# AVR16_BlueBoard.net
KiCad netlist of a schematic drawn in Altium Designer
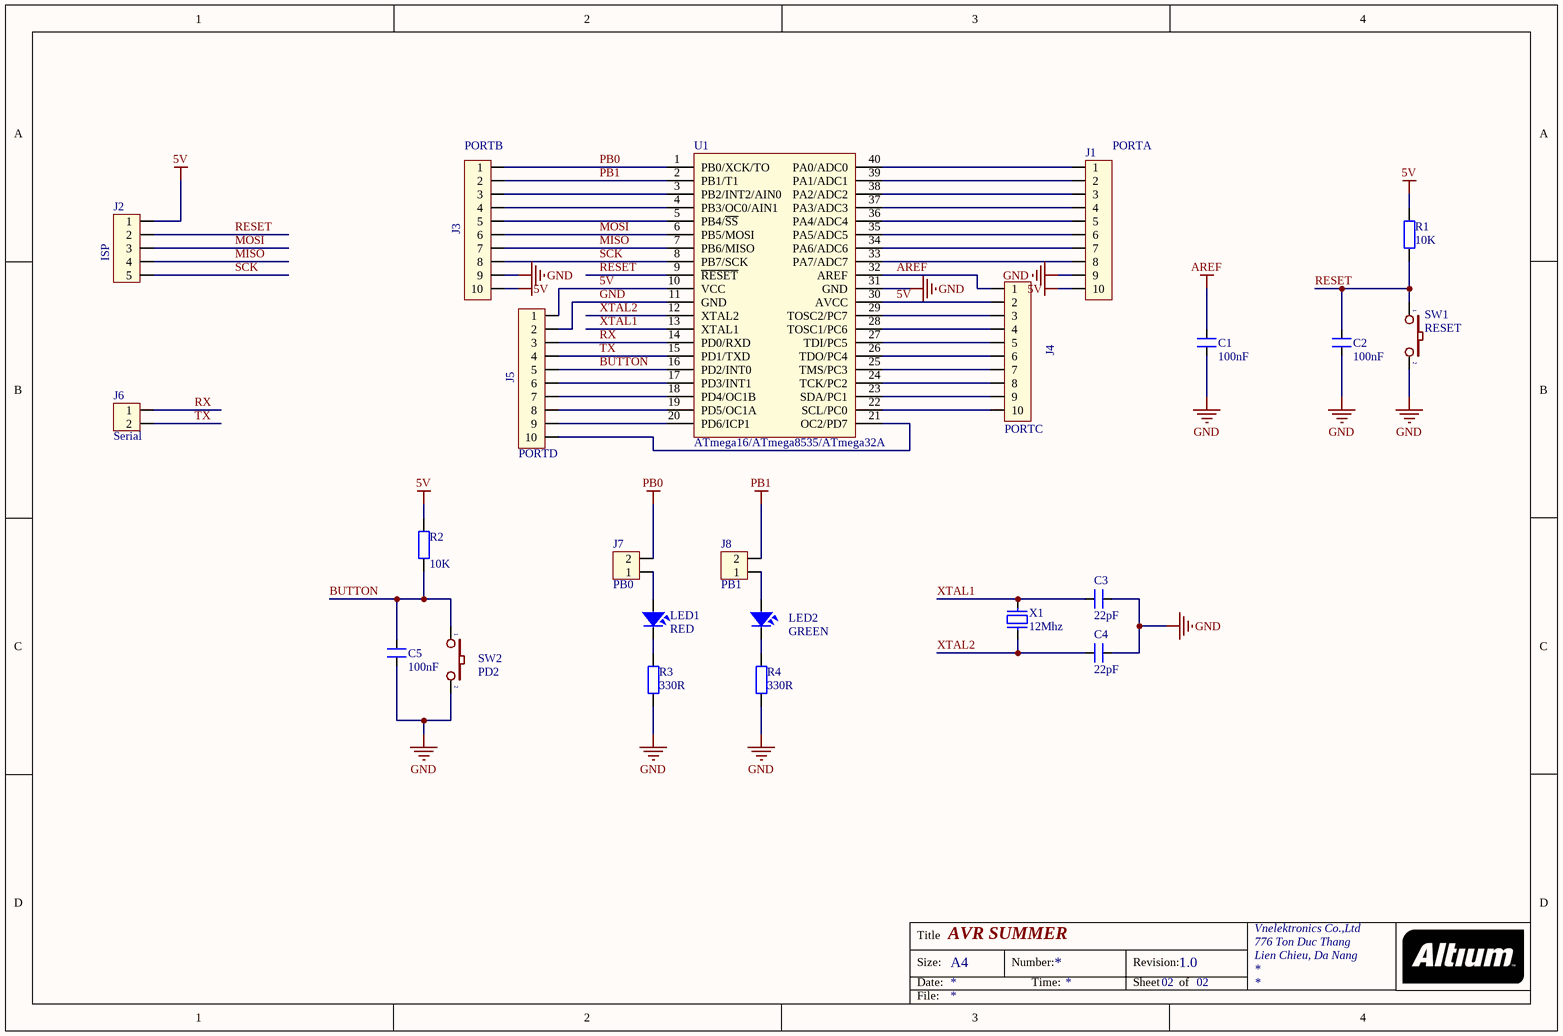
[diagram p0: AVR16 BlueBoard.SchDoc]

(export (version "E")
  (design (tool "Eeschema 10.0.6"))
  (components
    (comp (ref "C1")
      (value "100nF")
      (footprint "C0805")
      (description "Cap np  1pF - 472pF")
      (libsource (lib "syhaunguyen") (part "CN1"))
    )
    (comp (ref "C2")
      (value "100nF")
      (footprint "C0805")
      (description "Cap np  1pF - 472pF")
      (libsource (lib "syhaunguyen") (part "CN1"))
    )
    (comp (ref "C3")
      (value "22pF")
      (footprint "C0603")
      (description "Cap np  1pF - 472pF")
      (libsource (lib "syhaunguyen") (part "CN1"))
    )
    (comp (ref "C4")
      (value "22pF")
      (footprint "C0603")
      (description "Cap np  1pF - 472pF")
      (libsource (lib "syhaunguyen") (part "CN1"))
    )
    (comp (ref "C5")
      (value "100nF")
      (footprint "C0805")
      (description "Cap np  1pF - 472pF")
      (libsource (lib "syhaunguyen") (part "CN1"))
    )
    (comp (ref "J1")
      (value "PORTA")
      (footprint "Header_10")
      (description "Header 10")
      (libsource (lib "Tran Tuan") (part "Hed10"))
    )
    (comp (ref "J2")
      (value "ISP")
      (footprint "Header_5")
      (description "Header 5 (Green)")
      (libsource (lib "Tran Tuan") (part "Hed5"))
    )
    (comp (ref "J3")
      (value "PORTB")
      (footprint "Header_10")
      (description "Header 10")
      (libsource (lib "") (part "Hed10_1"))
    )
    (comp (ref "J4")
      (value "PORTC")
      (footprint "Header_10")
      (description "Header 10")
      (libsource (lib "Tran Tuan") (part "Hed10"))
    )
    (comp (ref "J5")
      (value "PORTD")
      (footprint "Header_10")
      (description "Header 10")
      (libsource (lib "") (part "Hed10_1"))
    )
    (comp (ref "J6")
      (value "Serial")
      (footprint "Header_2")
      (description "Header 2 (Green)")
      (libsource (lib "syhaunguyen") (part "Hed2"))
    )
    (comp (ref "J7")
      (value "PB0")
      (footprint "Header_2")
      (description "Header 2 (Green)")
      (libsource (lib "") (part "Hed2_1"))
    )
    (comp (ref "J8")
      (value "PB1")
      (footprint "Header_2")
      (description "Header 2 (Green)")
      (libsource (lib "") (part "Hed2_1"))
    )
    (comp (ref "LED1")
      (value "RED")
      (footprint "Led 0805R")
      (description "LED Single colour Green and Red")
      (libsource (lib "syhaunguyen") (part "LED"))
    )
    (comp (ref "LED2")
      (value "GREEN")
      (footprint "Led 0805G")
      (description "LED Single colour Green and Red")
      (libsource (lib "syhaunguyen") (part "LED"))
    )
    (comp (ref "R1")
      (value "10K")
      (footprint "RESC2012(0805)")
      (description "Resistor")
      (fields (field (name "Comment") "Res2") (field (name "PUBLISHER") "Altium Limited"))
      (libsource (lib "") (part "Res2_1"))
    )
    (comp (ref "R2")
      (value "10K")
      (footprint "RESC2012(0805)")
      (description "Resistor")
      (fields (field (name "Comment") "Res2") (field (name "PUBLISHER") "Altium Limited"))
      (libsource (lib "") (part "Res2_1"))
    )
    (comp (ref "R3")
      (value "330R")
      (footprint "RESC2012(0805)")
      (description "Resistor")
      (fields (field (name "Comment") "Res2") (field (name "PUBLISHER") "Altium Limited"))
      (libsource (lib "Miscellaneous Devices") (part "Res2"))
    )
    (comp (ref "R4")
      (value "330R")
      (footprint "RESC2012(0805)")
      (description "Resistor")
      (fields (field (name "Comment") "Res2") (field (name "PUBLISHER") "Altium Limited"))
      (libsource (lib "Miscellaneous Devices") (part "Res2"))
    )
    (comp (ref "SW1")
      (value "RESET")
      (footprint "BUTTON 2PIN TRON")
      (description "Switch button 2 pin")
      (libsource (lib "VNELEK") (part "SW2"))
    )
    (comp (ref "SW2")
      (value "PD2")
      (footprint "BUTTON 2PIN TRON")
      (description "Switch button 2 pin")
      (libsource (lib "VNELEK") (part "SW2"))
    )
    (comp (ref "U1")
      (value "ATmega16/ATmega8535/ATmega32A")
      (footprint "de gat xanh dip 40")
      (description "8-Bit AVR Microcontroller with 16K Bytes of In-System Programmable Flash Memory")
      (libsource (lib "Tran Tuan") (part "Atmega16L"))
    )
    (comp (ref "X1")
      (value "12Mhz")
      (footprint "CRYSTAL")
      (description "Crystal For all Crystal 2pin.")
      (libsource (lib "syhaunguyen") (part "XT2"))
    )
  )
  (nets
    (net (code "1") (name "/BUTTON") (class "Default")
      (node (ref "C5") (pin "1") (pinfunction "1_1") (pintype "passive"))
      (node (ref "J5") (pin "5") (pinfunction "5_5") (pintype "passive"))
      (node (ref "R2") (pin "1") (pinfunction "1_1") (pintype "passive"))
      (node (ref "SW2") (pin "1") (pinfunction "1_1") (pintype "passive"))
      (node (ref "U1") (pin "16") (pinfunction "PD2/INT0_16") (pintype "passive"))
    )
    (net (code "2") (name "/MISO") (class "Default")
      (node (ref "J2") (pin "4") (pinfunction "4_4") (pintype "passive"))
      (node (ref "J3") (pin "7") (pinfunction "7_7") (pintype "passive"))
      (node (ref "U1") (pin "7") (pinfunction "PB6/MISO_7") (pintype "passive"))
    )
    (net (code "3") (name "/MOSI") (class "Default")
      (node (ref "J2") (pin "3") (pinfunction "3_3") (pintype "passive"))
      (node (ref "J3") (pin "6") (pinfunction "6_6") (pintype "passive"))
      (node (ref "U1") (pin "6") (pinfunction "PB5/MOSI_6") (pintype "passive"))
    )
    (net (code "4") (name "/RESET") (class "Default")
      (node (ref "C2") (pin "1") (pinfunction "1_1") (pintype "passive"))
      (node (ref "J2") (pin "2") (pinfunction "2_2") (pintype "passive"))
      (node (ref "R1") (pin "1") (pinfunction "1_1") (pintype "passive"))
      (node (ref "SW1") (pin "1") (pinfunction "1_1") (pintype "passive"))
      (node (ref "U1") (pin "9") (pinfunction "~{RESET}_9") (pintype "passive"))
    )
    (net (code "5") (name "/RX") (class "Default")
      (node (ref "J5") (pin "3") (pinfunction "3_3") (pintype "passive"))
      (node (ref "J6") (pin "1") (pinfunction "1_1") (pintype "passive"))
      (node (ref "U1") (pin "14") (pinfunction "PD0/RXD_14") (pintype "passive"))
    )
    (net (code "6") (name "/SCK") (class "Default")
      (node (ref "J2") (pin "5") (pinfunction "5_5") (pintype "passive"))
      (node (ref "J3") (pin "8") (pinfunction "8_8") (pintype "passive"))
      (node (ref "U1") (pin "8") (pinfunction "PB7/SCK_8") (pintype "passive"))
    )
    (net (code "7") (name "/TX") (class "Default")
      (node (ref "J5") (pin "4") (pinfunction "4_4") (pintype "passive"))
      (node (ref "J6") (pin "2") (pinfunction "2_2") (pintype "passive"))
      (node (ref "U1") (pin "15") (pinfunction "PD1/TXD_15") (pintype "passive"))
    )
    (net (code "8") (name "/XTAL1") (class "Default")
      (node (ref "C3") (pin "2") (pinfunction "2_2") (pintype "passive"))
      (node (ref "U1") (pin "13") (pinfunction "XTAL1_13") (pintype "passive"))
      (node (ref "X1") (pin "1") (pinfunction "1_1") (pintype "passive"))
    )
    (net (code "9") (name "/XTAL2") (class "Default")
      (node (ref "C4") (pin "2") (pinfunction "2_2") (pintype "passive"))
      (node (ref "U1") (pin "12") (pinfunction "XTAL2_12") (pintype "passive"))
      (node (ref "X1") (pin "2") (pinfunction "2_2") (pintype "passive"))
    )
    (net (code "10") (name "5V") (class "Default")
      (node (ref "J1") (pin "10") (pinfunction "10_10") (pintype "passive"))
      (node (ref "J2") (pin "1") (pinfunction "1_1") (pintype "passive"))
      (node (ref "J3") (pin "10") (pinfunction "10_10") (pintype "passive"))
      (node (ref "J4") (pin "2") (pinfunction "2_2") (pintype "passive"))
      (node (ref "J5") (pin "1") (pinfunction "1_1") (pintype "passive"))
      (node (ref "R1") (pin "2") (pinfunction "2_2") (pintype "passive"))
      (node (ref "R2") (pin "2") (pinfunction "2_2") (pintype "passive"))
      (node (ref "U1") (pin "10") (pinfunction "VCC_10") (pintype "passive"))
      (node (ref "U1") (pin "30") (pinfunction "AVCC_30") (pintype "passive"))
    )
    (net (code "11") (name "AREF") (class "Default")
      (node (ref "C1") (pin "2") (pinfunction "2_2") (pintype "passive"))
      (node (ref "J4") (pin "1") (pinfunction "1_1") (pintype "passive"))
      (node (ref "U1") (pin "32") (pinfunction "AREF_32") (pintype "passive"))
    )
    (net (code "12") (name "GND") (class "Default")
      (node (ref "C1") (pin "1") (pinfunction "1_1") (pintype "passive"))
      (node (ref "C2") (pin "2") (pinfunction "2_2") (pintype "passive"))
      (node (ref "C3") (pin "1") (pinfunction "1_1") (pintype "passive"))
      (node (ref "C4") (pin "1") (pinfunction "1_1") (pintype "passive"))
      (node (ref "C5") (pin "2") (pinfunction "2_2") (pintype "passive"))
      (node (ref "J1") (pin "9") (pinfunction "9_9") (pintype "passive"))
      (node (ref "J3") (pin "9") (pinfunction "9_9") (pintype "passive"))
      (node (ref "J5") (pin "2") (pinfunction "2_2") (pintype "passive"))
      (node (ref "R3") (pin "2") (pinfunction "2_2") (pintype "passive"))
      (node (ref "R4") (pin "2") (pinfunction "2_2") (pintype "passive"))
      (node (ref "SW1") (pin "2") (pinfunction "2_2") (pintype "passive"))
      (node (ref "SW2") (pin "2") (pinfunction "2_2") (pintype "passive"))
      (node (ref "U1") (pin "11") (pinfunction "GND_11") (pintype "passive"))
      (node (ref "U1") (pin "31") (pinfunction "GND_31") (pintype "passive"))
    )
    (net (code "13") (name "Net-(J7-Pad1)") (class "Default")
      (node (ref "J7") (pin "1") (pinfunction "1_1") (pintype "passive"))
      (node (ref "LED1") (pin "1") (pinfunction "1_1") (pintype "passive"))
    )
    (net (code "14") (name "Net-(J8-Pad1)") (class "Default")
      (node (ref "J8") (pin "1") (pinfunction "1_1") (pintype "passive"))
      (node (ref "LED2") (pin "1") (pinfunction "1_1") (pintype "passive"))
    )
    (net (code "15") (name "Net-(LED1-Pad2)") (class "Default")
      (node (ref "LED1") (pin "2") (pinfunction "2_2") (pintype "passive"))
      (node (ref "R3") (pin "1") (pinfunction "1_1") (pintype "passive"))
    )
    (net (code "16") (name "Net-(LED2-Pad2)") (class "Default")
      (node (ref "LED2") (pin "2") (pinfunction "2_2") (pintype "passive"))
      (node (ref "R4") (pin "1") (pinfunction "1_1") (pintype "passive"))
    )
    (net (code "17") (name "Net-(U1-OC2{slash}PD7)") (class "Default")
      (node (ref "J5") (pin "10") (pinfunction "10_10") (pintype "passive"))
      (node (ref "U1") (pin "21") (pinfunction "OC2/PD7_21") (pintype "passive"))
    )
    (net (code "18") (name "Net-(U1-PA0{slash}ADC0)") (class "Default")
      (node (ref "J1") (pin "1") (pinfunction "1_1") (pintype "passive"))
      (node (ref "U1") (pin "40") (pinfunction "PA0/ADC0_40") (pintype "passive"))
    )
    (net (code "19") (name "Net-(U1-PA1{slash}ADC1)") (class "Default")
      (node (ref "J1") (pin "2") (pinfunction "2_2") (pintype "passive"))
      (node (ref "U1") (pin "39") (pinfunction "PA1/ADC1_39") (pintype "passive"))
    )
    (net (code "20") (name "Net-(U1-PA2{slash}ADC2)") (class "Default")
      (node (ref "J1") (pin "3") (pinfunction "3_3") (pintype "passive"))
      (node (ref "U1") (pin "38") (pinfunction "PA2/ADC2_38") (pintype "passive"))
    )
    (net (code "21") (name "Net-(U1-PA3{slash}ADC3)") (class "Default")
      (node (ref "J1") (pin "4") (pinfunction "4_4") (pintype "passive"))
      (node (ref "U1") (pin "37") (pinfunction "PA3/ADC3_37") (pintype "passive"))
    )
    (net (code "22") (name "Net-(U1-PA4{slash}ADC4)") (class "Default")
      (node (ref "J1") (pin "5") (pinfunction "5_5") (pintype "passive"))
      (node (ref "U1") (pin "36") (pinfunction "PA4/ADC4_36") (pintype "passive"))
    )
    (net (code "23") (name "Net-(U1-PA5{slash}ADC5)") (class "Default")
      (node (ref "J1") (pin "6") (pinfunction "6_6") (pintype "passive"))
      (node (ref "U1") (pin "35") (pinfunction "PA5/ADC5_35") (pintype "passive"))
    )
    (net (code "24") (name "Net-(U1-PA6{slash}ADC6)") (class "Default")
      (node (ref "J1") (pin "7") (pinfunction "7_7") (pintype "passive"))
      (node (ref "U1") (pin "34") (pinfunction "PA6/ADC6_34") (pintype "passive"))
    )
    (net (code "25") (name "Net-(U1-PA7{slash}ADC7)") (class "Default")
      (node (ref "J1") (pin "8") (pinfunction "8_8") (pintype "passive"))
      (node (ref "U1") (pin "33") (pinfunction "PA7/ADC7_33") (pintype "passive"))
    )
    (net (code "26") (name "Net-(U1-PB2{slash}INT2{slash}AIN0)") (class "Default")
      (node (ref "J3") (pin "3") (pinfunction "3_3") (pintype "passive"))
      (node (ref "U1") (pin "3") (pinfunction "PB2/INT2/AIN0_3") (pintype "passive"))
    )
    (net (code "27") (name "Net-(U1-PB3{slash}OC0{slash}AIN1)") (class "Default")
      (node (ref "J3") (pin "4") (pinfunction "4_4") (pintype "passive"))
      (node (ref "U1") (pin "4") (pinfunction "PB3/OC0/AIN1_4") (pintype "passive"))
    )
    (net (code "28") (name "Net-(U1-PB4{slash}~{SS})") (class "Default")
      (node (ref "J3") (pin "5") (pinfunction "5_5") (pintype "passive"))
      (node (ref "U1") (pin "5") (pinfunction "PB4/~{SS}_5") (pintype "passive"))
    )
    (net (code "29") (name "Net-(U1-PD3{slash}INT1)") (class "Default")
      (node (ref "J5") (pin "6") (pinfunction "6_6") (pintype "passive"))
      (node (ref "U1") (pin "17") (pinfunction "PD3/INT1_17") (pintype "passive"))
    )
    (net (code "30") (name "Net-(U1-PD4{slash}OC1B)") (class "Default")
      (node (ref "J5") (pin "7") (pinfunction "7_7") (pintype "passive"))
      (node (ref "U1") (pin "18") (pinfunction "PD4/OC1B_18") (pintype "passive"))
    )
    (net (code "31") (name "Net-(U1-PD5{slash}OC1A)") (class "Default")
      (node (ref "J5") (pin "8") (pinfunction "8_8") (pintype "passive"))
      (node (ref "U1") (pin "19") (pinfunction "PD5/OC1A_19") (pintype "passive"))
    )
    (net (code "32") (name "Net-(U1-PD6{slash}ICP1)") (class "Default")
      (node (ref "J5") (pin "9") (pinfunction "9_9") (pintype "passive"))
      (node (ref "U1") (pin "20") (pinfunction "PD6/ICP1_20") (pintype "passive"))
    )
    (net (code "33") (name "Net-(U1-SCL{slash}PC0)") (class "Default")
      (node (ref "J4") (pin "10") (pinfunction "10_10") (pintype "passive"))
      (node (ref "U1") (pin "22") (pinfunction "SCL/PC0_22") (pintype "passive"))
    )
    (net (code "34") (name "Net-(U1-SDA{slash}PC1)") (class "Default")
      (node (ref "J4") (pin "9") (pinfunction "9_9") (pintype "passive"))
      (node (ref "U1") (pin "23") (pinfunction "SDA/PC1_23") (pintype "passive"))
    )
    (net (code "35") (name "Net-(U1-TCK{slash}PC2)") (class "Default")
      (node (ref "J4") (pin "8") (pinfunction "8_8") (pintype "passive"))
      (node (ref "U1") (pin "24") (pinfunction "TCK/PC2_24") (pintype "passive"))
    )
    (net (code "36") (name "Net-(U1-TDI{slash}PC5)") (class "Default")
      (node (ref "J4") (pin "5") (pinfunction "5_5") (pintype "passive"))
      (node (ref "U1") (pin "27") (pinfunction "TDI/PC5_27") (pintype "passive"))
    )
    (net (code "37") (name "Net-(U1-TDO{slash}PC4)") (class "Default")
      (node (ref "J4") (pin "6") (pinfunction "6_6") (pintype "passive"))
      (node (ref "U1") (pin "26") (pinfunction "TDO/PC4_26") (pintype "passive"))
    )
    (net (code "38") (name "Net-(U1-TMS{slash}PC3)") (class "Default")
      (node (ref "J4") (pin "7") (pinfunction "7_7") (pintype "passive"))
      (node (ref "U1") (pin "25") (pinfunction "TMS/PC3_25") (pintype "passive"))
    )
    (net (code "39") (name "Net-(U1-TOSC1{slash}PC6)") (class "Default")
      (node (ref "J4") (pin "4") (pinfunction "4_4") (pintype "passive"))
      (node (ref "U1") (pin "28") (pinfunction "TOSC1/PC6_28") (pintype "passive"))
    )
    (net (code "40") (name "Net-(U1-TOSC2{slash}PC7)") (class "Default")
      (node (ref "J4") (pin "3") (pinfunction "3_3") (pintype "passive"))
      (node (ref "U1") (pin "29") (pinfunction "TOSC2/PC7_29") (pintype "passive"))
    )
    (net (code "41") (name "PB0") (class "Default")
      (node (ref "J3") (pin "1") (pinfunction "1_1") (pintype "passive"))
      (node (ref "J7") (pin "2") (pinfunction "2_2") (pintype "passive"))
      (node (ref "U1") (pin "1") (pinfunction "PB0/XCK/TO_1") (pintype "passive"))
    )
    (net (code "42") (name "PB1") (class "Default")
      (node (ref "J3") (pin "2") (pinfunction "2_2") (pintype "passive"))
      (node (ref "J8") (pin "2") (pinfunction "2_2") (pintype "passive"))
      (node (ref "U1") (pin "2") (pinfunction "PB1/T1_2") (pintype "passive"))
    )
  )
)
